# demo_V1_1.net
KiCad netlist of a schematic drawn in Altium Designer
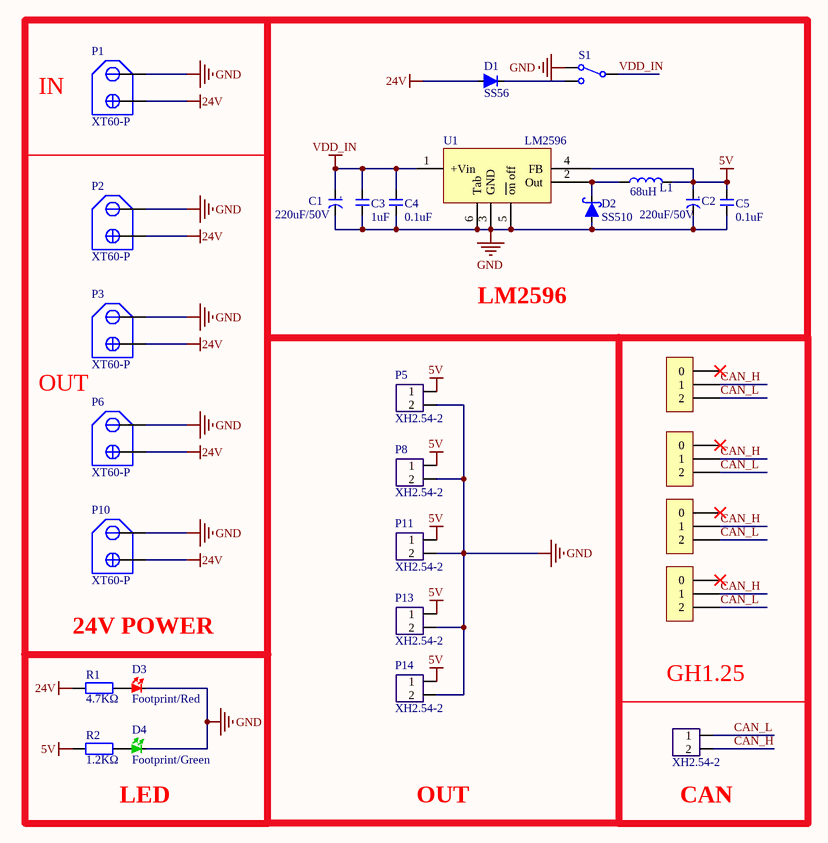
[diagram p0: demo V1.1.SchDoc]

(export (version "E")
  (design (tool "Eeschema 10.0.6"))
  (components
    (comp (ref "C1")
      (value "Device Name")
      (footprint "CAP Elec 5.0-10.0X20.0(φ0.6)")
      (description "CAP Aluminum Electrolytic")
      (fields (field (name "SCH NAME") "220uF/50V"))
      (libsource (lib "Basal") (part "CAP Elec"))
    )
    (comp (ref "C2")
      (value "Device Name")
      (footprint "CAP Elec 5.0-10.0X20.0(φ0.6)")
      (description "CAP Aluminum Electrolytic")
      (fields (field (name "SCH NAME") "220uF/50V"))
      (libsource (lib "Basal") (part "CAP Elec"))
    )
    (comp (ref "C3")
      (value "xxuF/xxV/Footprint")
      (footprint "CAP MLCC 0603")
      (description "CAP MLCC")
      (fields (field (name "SCH NAME") "1uF"))
      (libsource (lib "Basal") (part "CAP MLCC"))
    )
    (comp (ref "C4")
      (value "xxuF/xxV/Footprint")
      (footprint "CAP MLCC 0603")
      (description "CAP MLCC")
      (fields (field (name "SCH NAME") "0.1uF"))
      (libsource (lib "Basal") (part "CAP MLCC"))
    )
    (comp (ref "C5")
      (value "xxuF/xxV/Footprint")
      (footprint "CAP MLCC 0603")
      (description "CAP MLCC")
      (fields (field (name "SCH NAME") "0.1uF"))
      (libsource (lib "Basal") (part "CAP MLCC"))
    )
    (comp (ref "D1")
      (value "SS56")
      (footprint "DIODE SMA(DO-214AC)")
      (description "Diode Rectifier")
      (fields (field (name "SCH NAME") "SS56"))
      (libsource (lib "Basal") (part "Diode Rectifier"))
    )
    (comp (ref "D2")
      (value "SS510")
      (footprint "DIODE SMA(DO-214AC)")
      (description "Diode Schottky")
      (fields (field (name "SCH NAME") "SS510"))
      (libsource (lib "Basal") (part "Diode Schottky"))
    )
    (comp (ref "D3")
      (value "Device Name")
      (footprint "LED_0805_R")
      (description "LED Red")
      (fields (field (name "SCH NAME") "Footprint/Red"))
      (libsource (lib "Basal") (part "LED Red"))
    )
    (comp (ref "D4")
      (value "Device Name")
      (footprint "LED_0805_G")
      (description "LED Green")
      (fields (field (name "SCH NAME") "Footprint/Green"))
      (libsource (lib "Basal") (part "LED Green"))
    )
    (comp (ref "L1")
      (value "Device Name")
      (footprint "INDC SMDP 7447709(12X12X10)")
      (description "Inductor SMD Power")
      (fields (field (name "SCH NAME") "68uH"))
      (libsource (lib "Basal") (part "Inductor SMD Power"))
    )
    (comp (ref "P1")
      (value "XT60-P")
      (footprint "XT60-P")
      (description "XT Connector")
      (fields (field (name "SCH NAME") "XT60-P"))
      (libsource (lib "Connector") (part "XT60-P"))
    )
    (comp (ref "P2")
      (value "XT60-P")
      (footprint "XT60-P")
      (description "XT Connector")
      (fields (field (name "SCH NAME") "XT60-P"))
      (libsource (lib "Connector") (part "XT60-P"))
    )
    (comp (ref "P3")
      (value "XT60-P")
      (footprint "XT60-P")
      (description "XT Connector")
      (fields (field (name "SCH NAME") "XT60-P"))
      (libsource (lib "Connector") (part "XT60-P"))
    )
    (comp (ref "P4")
      (value "BM02B-GHS-TBT")
      (footprint "JST BM02B-GHS-TBT")
      (libsource (lib "Connector") (part "JST BM02B-GHS-TBT"))
    )
    (comp (ref "P5")
      (value "XH2.54-2")
      (footprint "XH2.54_2AW")
      (fields (field (name "SCH NAME") "XH2.54-2"))
      (libsource (lib "Connector") (part "XH2.54-2"))
    )
    (comp (ref "P6")
      (value "XT60-P")
      (footprint "XT60-P")
      (description "XT Connector")
      (fields (field (name "SCH NAME") "XT60-P"))
      (libsource (lib "Connector") (part "XT60-P"))
    )
    (comp (ref "P7")
      (value "BM02B-GHS-TBT")
      (footprint "JST BM02B-GHS-TBT")
      (libsource (lib "Connector") (part "JST BM02B-GHS-TBT"))
    )
    (comp (ref "P8")
      (value "XH2.54-2")
      (footprint "XH2.54_2AW")
      (fields (field (name "SCH NAME") "XH2.54-2"))
      (libsource (lib "Connector") (part "XH2.54-2"))
    )
    (comp (ref "P9")
      (value "BM02B-GHS-TBT")
      (footprint "JST BM02B-GHS-TBT")
      (libsource (lib "Connector") (part "JST BM02B-GHS-TBT"))
    )
    (comp (ref "P10")
      (value "XT60-P")
      (footprint "XT60-P")
      (description "XT Connector")
      (fields (field (name "SCH NAME") "XT60-P"))
      (libsource (lib "Connector") (part "XT60-P"))
    )
    (comp (ref "P11")
      (value "XH2.54-2")
      (footprint "XH2.54_2AW")
      (fields (field (name "SCH NAME") "XH2.54-2"))
      (libsource (lib "Connector") (part "XH2.54-2"))
    )
    (comp (ref "P12")
      (value "BM02B-GHS-TBT")
      (footprint "JST BM02B-GHS-TBT")
      (libsource (lib "Connector") (part "JST BM02B-GHS-TBT"))
    )
    (comp (ref "P13")
      (value "XH2.54-2")
      (footprint "XH2.54_2AW")
      (fields (field (name "SCH NAME") "XH2.54-2"))
      (libsource (lib "Connector") (part "XH2.54-2"))
    )
    (comp (ref "P14")
      (value "XH2.54-2")
      (footprint "XH2.54_2AW")
      (fields (field (name "SCH NAME") "XH2.54-2"))
      (libsource (lib "Connector") (part "XH2.54-2"))
    )
    (comp (ref "P15")
      (value "XH2.54-2")
      (footprint "XH2.54_2AW")
      (fields (field (name "SCH NAME") "XH2.54-2"))
      (libsource (lib "Connector") (part "XH2.54-2"))
    )
    (comp (ref "R1")
      (value "4.7KΩ")
      (footprint "0603_R")
      (description "贴片电阻")
      (libsource (lib "RES") (part "0603 4.7KΩ (4701) 1%"))
    )
    (comp (ref "R2")
      (value "1.2KΩ")
      (footprint "0603_R")
      (description "贴片电阻")
      (libsource (lib "RES") (part "0603 1.2KΩ (1201) 1%"))
    )
    (comp (ref "S1")
      (value "Device Name")
      (footprint "SWITCH  Rocker 3-21.4x15")
      (description "船型开关")
      (libsource (lib "Other") (part "Switch Rocker"))
    )
    (comp (ref "U1") (value "LM2596") (footprint "TO263-5") (libsource (lib "IC_TI") (part "LM2596")))
  )
  (nets
    (net (code "1") (name "/CAN_H") (class "Default")
      (node (ref "P12") (pin "1") (pinfunction "1_1") (pintype "power_in"))
      (node (ref "P15") (pin "2") (pinfunction "2_2") (pintype "passive"))
      (node (ref "P4") (pin "1") (pinfunction "1_1") (pintype "power_in"))
      (node (ref "P7") (pin "1") (pinfunction "1_1") (pintype "power_in"))
      (node (ref "P9") (pin "1") (pinfunction "1_1") (pintype "power_in"))
    )
    (net (code "2") (name "/CAN_L") (class "Default")
      (node (ref "P12") (pin "2") (pinfunction "2_2") (pintype "power_in"))
      (node (ref "P15") (pin "1") (pinfunction "1_1") (pintype "passive"))
      (node (ref "P4") (pin "2") (pinfunction "2_2") (pintype "power_in"))
      (node (ref "P7") (pin "2") (pinfunction "2_2") (pintype "power_in"))
      (node (ref "P9") (pin "2") (pinfunction "2_2") (pintype "power_in"))
    )
    (net (code "3") (name "5V") (class "Default")
      (node (ref "C2") (pin "1") (pintype "passive"))
      (node (ref "C5") (pin "2") (pintype "passive"))
      (node (ref "L1") (pin "2") (pinfunction "2_2") (pintype "passive"))
      (node (ref "P11") (pin "1") (pinfunction "1_1") (pintype "passive"))
      (node (ref "P13") (pin "1") (pinfunction "1_1") (pintype "passive"))
      (node (ref "P14") (pin "1") (pinfunction "1_1") (pintype "passive"))
      (node (ref "P5") (pin "1") (pinfunction "1_1") (pintype "passive"))
      (node (ref "P8") (pin "1") (pinfunction "1_1") (pintype "passive"))
      (node (ref "R2") (pin "1") (pinfunction "1_1") (pintype "passive"))
      (node (ref "U1") (pin "4") (pinfunction "FB_4") (pintype "passive"))
    )
    (net (code "4") (name "24V") (class "Default")
      (node (ref "D1") (pin "1") (pinfunction "A_1") (pintype "passive"))
      (node (ref "P1") (pin "1") (pinfunction "+_1") (pintype "power_in"))
      (node (ref "P10") (pin "1") (pinfunction "+_1") (pintype "power_in"))
      (node (ref "P2") (pin "1") (pinfunction "+_1") (pintype "power_in"))
      (node (ref "P3") (pin "1") (pinfunction "+_1") (pintype "power_in"))
      (node (ref "P6") (pin "1") (pinfunction "+_1") (pintype "power_in"))
      (node (ref "R1") (pin "1") (pinfunction "1_1") (pintype "passive"))
    )
    (net (code "5") (name "GND") (class "Default")
      (node (ref "C1") (pin "2") (pintype "passive"))
      (node (ref "C2") (pin "2") (pintype "passive"))
      (node (ref "C3") (pin "1") (pintype "passive"))
      (node (ref "C4") (pin "1") (pintype "passive"))
      (node (ref "C5") (pin "1") (pintype "passive"))
      (node (ref "D2") (pin "1") (pinfunction "A_1") (pintype "passive"))
      (node (ref "D3") (pin "2") (pintype "passive"))
      (node (ref "D4") (pin "2") (pintype "passive"))
      (node (ref "P1") (pin "2") (pinfunction "-_2") (pintype "power_in"))
      (node (ref "P10") (pin "2") (pinfunction "-_2") (pintype "power_in"))
      (node (ref "P11") (pin "2") (pinfunction "2_2") (pintype "passive"))
      (node (ref "P13") (pin "2") (pinfunction "2_2") (pintype "passive"))
      (node (ref "P14") (pin "2") (pinfunction "2_2") (pintype "passive"))
      (node (ref "P2") (pin "2") (pinfunction "-_2") (pintype "power_in"))
      (node (ref "P3") (pin "2") (pinfunction "-_2") (pintype "power_in"))
      (node (ref "P5") (pin "2") (pinfunction "2_2") (pintype "passive"))
      (node (ref "P6") (pin "2") (pinfunction "-_2") (pintype "power_in"))
      (node (ref "P8") (pin "2") (pinfunction "2_2") (pintype "passive"))
      (node (ref "S1") (pin "3") (pinfunction "NC_3") (pintype "passive"))
      (node (ref "U1") (pin "3") (pinfunction "GND_3") (pintype "passive"))
      (node (ref "U1") (pin "5") (pinfunction "~{on}_off_5") (pintype "passive"))
      (node (ref "U1") (pin "6") (pinfunction "Tab_6") (pintype "passive"))
    )
    (net (code "6") (name "Net-(D1-C)") (class "Default")
      (node (ref "D1") (pin "2") (pinfunction "C_2") (pintype "passive"))
      (node (ref "S1") (pin "2") (pinfunction "NO_2") (pintype "passive"))
    )
    (net (code "7") (name "Net-(D2-B)") (class "Default")
      (node (ref "D2") (pin "2") (pinfunction "B_2") (pintype "passive"))
      (node (ref "L1") (pin "1") (pinfunction "1_1") (pintype "passive"))
      (node (ref "U1") (pin "2") (pinfunction "Out_2") (pintype "passive"))
    )
    (net (code "8") (name "Net-(D3-Pad1)") (class "Default")
      (node (ref "D3") (pin "1") (pintype "passive"))
      (node (ref "R1") (pin "2") (pinfunction "2_2") (pintype "passive"))
    )
    (net (code "9") (name "Net-(D4-Pad1)") (class "Default")
      (node (ref "D4") (pin "1") (pintype "passive"))
      (node (ref "R2") (pin "2") (pinfunction "2_2") (pintype "passive"))
    )
    (net (code "10") (name "VDD_IN") (class "Default")
      (node (ref "C1") (pin "1") (pintype "passive"))
      (node (ref "C3") (pin "2") (pintype "passive"))
      (node (ref "C4") (pin "2") (pintype "passive"))
      (node (ref "S1") (pin "1") (pinfunction "COMMON_1") (pintype "passive"))
      (node (ref "U1") (pin "1") (pinfunction "+Vin_1") (pintype "passive"))
    )
    (net (code "11") (name "unconnected-(P4-Pad0)") (class "Default")
      (node (ref "P4") (pin "0") (pinfunction "0_0") (pintype "power_in+no_connect"))
    )
    (net (code "12") (name "unconnected-(P7-Pad0)") (class "Default")
      (node (ref "P7") (pin "0") (pinfunction "0_0") (pintype "power_in+no_connect"))
    )
    (net (code "13") (name "unconnected-(P9-Pad0)") (class "Default")
      (node (ref "P9") (pin "0") (pinfunction "0_0") (pintype "power_in+no_connect"))
    )
    (net (code "14") (name "unconnected-(P12-Pad0)") (class "Default")
      (node (ref "P12") (pin "0") (pinfunction "0_0") (pintype "power_in+no_connect"))
    )
  )
)
